# electro.net
KiCad netlist of a schematic drawn in EAGLE
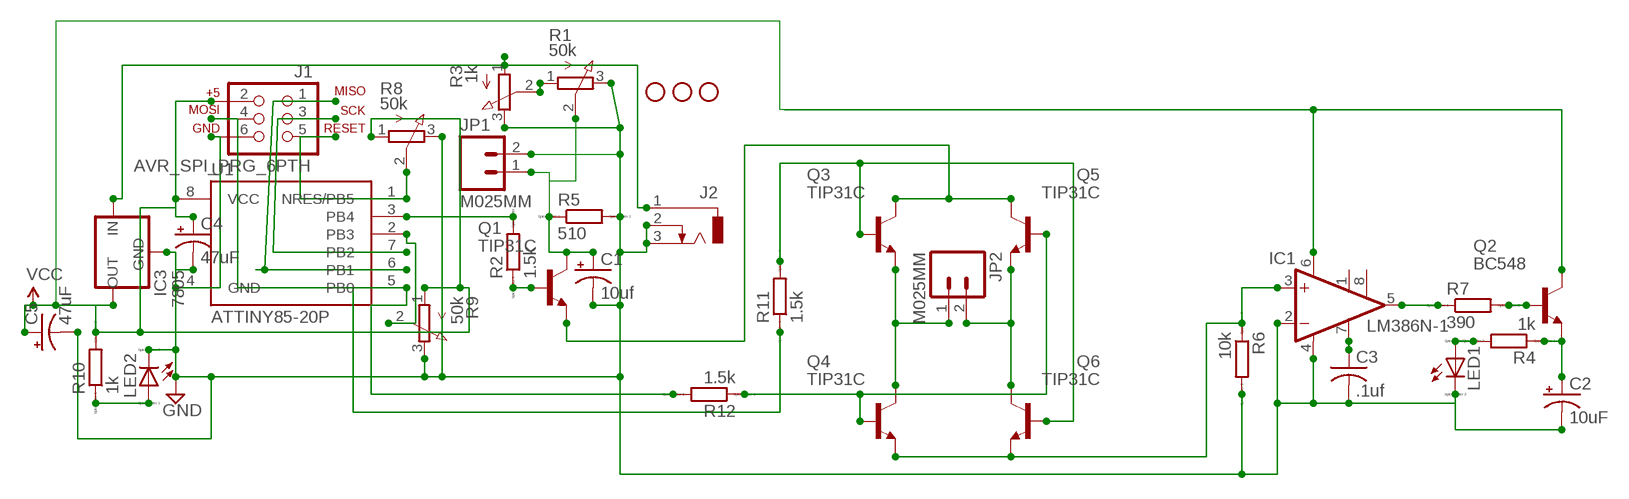
[diagram p0: schematic, sheet 1]

(export (version "E")
  (design (tool "Eeschema 10.0.6"))
  (components
    (comp (ref "C1")
      (value "10uf")
      (footprint "eagle-import:E2,5-6E")
      (libsource (lib "eagle-import") (part "CPOL-USE2,5-6E"))
    )
    (comp (ref "C2")
      (value "10uF")
      (footprint "eagle-import:E2,5-6E")
      (libsource (lib "eagle-import") (part "CPOL-USE2,5-6E"))
    )
    (comp (ref "C3")
      (value ".1uf")
      (footprint "eagle-import:C025-025X050")
      (libsource (lib "eagle-import") (part "C-US025-025X050"))
    )
    (comp (ref "C4")
      (value "47uF")
      (footprint "eagle-import:E2,5-6")
      (libsource (lib "eagle-import") (part "CPOL-USE2.5-6"))
    )
    (comp (ref "C5")
      (value "47uF")
      (footprint "eagle-import:E2,5-6")
      (libsource (lib "eagle-import") (part "CPOL-USE2.5-6"))
    )
    (comp (ref "IC1")
      (value "LM386N-1")
      (footprint "eagle-import:DIL08")
      (libsource (lib "eagle-import") (part "LM386?-N1"))
    )
    (comp (ref "IC3")
      (value "7805")
      (footprint "eagle-import:78XXL")
      (libsource (lib "eagle-import") (part "78XXL"))
    )
    (comp (ref "J1")
      (value "AVR_SPI_PRG_6PTH")
      (footprint "eagle-import:2X3")
      (libsource (lib "eagle-import") (part "AVR_SPI_PRG_6PTH"))
    )
    (comp (ref "J2")
      (value "DCJ0303")
      (footprint "eagle-import:DCJ0303")
      (libsource (lib "eagle-import") (part "DCJ0303"))
    )
    (comp (ref "JP1")
      (value "M025MM")
      (footprint "eagle-import:SCREWTERMINAL-5MM-2")
      (libsource (lib "eagle-import") (part "M025MM"))
    )
    (comp (ref "JP2")
      (value "M025MM")
      (footprint "eagle-import:SCREWTERMINAL-5MM-2")
      (libsource (lib "eagle-import") (part "M025MM"))
    )
    (comp (ref "LED1")
      (value "LED_ELD260")
      (footprint "eagle-import:LED_LD260")
      (libsource (lib "eagle-import") (part "LED_ELD260"))
    )
    (comp (ref "LED2")
      (value "LED_ELD260")
      (footprint "eagle-import:LED_LD260")
      (libsource (lib "eagle-import") (part "LED_ELD260"))
    )
    (comp (ref "Q1")
      (value "TIP31C")
      (footprint "eagle-import:TO220")
      (libsource (lib "eagle-import") (part "TIP31C"))
    )
    (comp (ref "Q2")
      (value "BC548")
      (footprint "eagle-import:TO92-EBC")
      (libsource (lib "eagle-import") (part "BC548"))
    )
    (comp (ref "Q3")
      (value "TIP31C")
      (footprint "eagle-import:TO220")
      (libsource (lib "eagle-import") (part "TIP31C"))
    )
    (comp (ref "Q4")
      (value "TIP31C")
      (footprint "eagle-import:TO220")
      (libsource (lib "eagle-import") (part "TIP31C"))
    )
    (comp (ref "Q5")
      (value "TIP31C")
      (footprint "eagle-import:TO220")
      (libsource (lib "eagle-import") (part "TIP31C"))
    )
    (comp (ref "Q6")
      (value "TIP31C")
      (footprint "eagle-import:TO220")
      (libsource (lib "eagle-import") (part "TIP31C"))
    )
    (comp (ref "R1")
      (value "50k")
      (footprint "eagle-import:3RP_1610N")
      (libsource (lib "eagle-import") (part "3RP/1610N"))
    )
    (comp (ref "R2")
      (value "1.5k")
      (footprint "eagle-import:0207_10")
      (libsource (lib "eagle-import") (part "R0207/10"))
    )
    (comp (ref "R3")
      (value "1k")
      (footprint "eagle-import:3RP_1610N")
      (libsource (lib "eagle-import") (part "3RP/1610N"))
    )
    (comp (ref "R4")
      (value "1k")
      (footprint "eagle-import:0207_10")
      (libsource (lib "eagle-import") (part "R0207/10"))
    )
    (comp (ref "R5")
      (value "510")
      (footprint "eagle-import:0207_10")
      (libsource (lib "eagle-import") (part "R0207/10"))
    )
    (comp (ref "R6")
      (value "10k")
      (footprint "eagle-import:0207_10")
      (libsource (lib "eagle-import") (part "R0207/10"))
    )
    (comp (ref "R7")
      (value "390")
      (footprint "eagle-import:0207_10")
      (libsource (lib "eagle-import") (part "R0207/10"))
    )
    (comp (ref "R8")
      (value "50k")
      (footprint "eagle-import:3RP_1610N")
      (libsource (lib "eagle-import") (part "3RP/1610N"))
    )
    (comp (ref "R9")
      (value "50k")
      (footprint "eagle-import:3RP_1610N")
      (libsource (lib "eagle-import") (part "3RP/1610N"))
    )
    (comp (ref "R10")
      (value "1k")
      (footprint "eagle-import:0207_10")
      (libsource (lib "eagle-import") (part "R0207/10"))
    )
    (comp (ref "R11")
      (value "1.5k")
      (footprint "eagle-import:0207_10")
      (libsource (lib "eagle-import") (part "R0207/10"))
    )
    (comp (ref "R12")
      (value "1.5k")
      (footprint "eagle-import:0207_10")
      (libsource (lib "eagle-import") (part "R0207/10"))
    )
    (comp (ref "STANDOFF2")
      (value "STAND-OFF")
      (footprint "eagle-import:STAND-OFF")
      (libsource (lib "eagle-import") (part "STAND-OFF"))
    )
    (comp (ref "STANDOFF3")
      (value "STAND-OFF")
      (footprint "eagle-import:STAND-OFF")
      (libsource (lib "eagle-import") (part "STAND-OFF"))
    )
    (comp (ref "STANDOFF4")
      (value "STAND-OFF")
      (footprint "eagle-import:STAND-OFF")
      (libsource (lib "eagle-import") (part "STAND-OFF"))
    )
    (comp (ref "U1")
      (value "ATTINY85-20P")
      (footprint "eagle-import:PDIP08_300MIL")
      (libsource (lib "eagle-import") (part "ATTINY85P-20"))
    )
  )
  (nets
    (net (code "1") (name "GND") (class "Default")
      (node (ref "C1") (pin "-") (pinfunction "-_-") (pintype "passive"))
      (node (ref "C2") (pin "-") (pinfunction "-_-") (pintype "passive"))
      (node (ref "C3") (pin "2") (pinfunction "2_2") (pintype "passive"))
      (node (ref "C4") (pin "-") (pinfunction "-_-") (pintype "passive"))
      (node (ref "C5") (pin "-") (pinfunction "-_-") (pintype "passive"))
      (node (ref "IC1") (pin "2") (pinfunction "-IN_2") (pintype "input"))
      (node (ref "IC1") (pin "4") (pinfunction "GND_4") (pintype "power_in"))
      (node (ref "IC3") (pin "GND") (pinfunction "GND_GND") (pintype "input"))
      (node (ref "J1") (pin "6") (pinfunction "6_6") (pintype "passive"))
      (node (ref "J2") (pin "2") (pinfunction "2_2") (pintype "passive"))
      (node (ref "J2") (pin "3") (pinfunction "3_3") (pintype "passive"))
      (node (ref "JP1") (pin "2") (pinfunction "2_2") (pintype "passive"))
      (node (ref "LED1") (pin "K") (pinfunction "C_K") (pintype "passive"))
      (node (ref "LED2") (pin "K") (pinfunction "C_K") (pintype "passive"))
      (node (ref "R1") (pin "3") (pinfunction "E_3") (pintype "passive"))
      (node (ref "R3") (pin "3") (pinfunction "E_3") (pintype "passive"))
      (node (ref "R5") (pin "2") (pinfunction "2_2") (pintype "passive"))
      (node (ref "R6") (pin "2") (pinfunction "2_2") (pintype "passive"))
      (node (ref "R8") (pin "3") (pinfunction "E_3") (pintype "passive"))
      (node (ref "R9") (pin "3") (pinfunction "E_3") (pintype "passive"))
      (node (ref "U1") (pin "4") (pinfunction "GND_4") (pintype "power_in"))
    )
    (net (code "2") (name "Net-(C2-Pad+)") (class "Default")
      (node (ref "C2") (pin "+") (pinfunction "+_+") (pintype "passive"))
      (node (ref "Q2") (pin "E") (pinfunction "E_E") (pintype "passive"))
      (node (ref "R4") (pin "1") (pinfunction "1_1") (pintype "passive"))
    )
    (net (code "3") (name "Net-(IC1-+IN)") (class "Default")
      (node (ref "IC1") (pin "3") (pinfunction "+IN_3") (pintype "input"))
      (node (ref "Q4") (pin "3") (pinfunction "E_3") (pintype "passive"))
      (node (ref "Q6") (pin "3") (pinfunction "E_3") (pintype "passive"))
      (node (ref "R6") (pin "1") (pinfunction "1_1") (pintype "passive"))
    )
    (net (code "4") (name "Net-(IC1-BYPASS)") (class "Default")
      (node (ref "C3") (pin "1") (pinfunction "1_1") (pintype "passive"))
      (node (ref "IC1") (pin "7") (pinfunction "BYPASS_7") (pintype "passive"))
    )
    (net (code "5") (name "Net-(IC1-OUT)") (class "Default")
      (node (ref "IC1") (pin "5") (pinfunction "OUT_5") (pintype "output"))
      (node (ref "R7") (pin "1") (pinfunction "1_1") (pintype "passive"))
    )
    (net (code "6") (name "Net-(LED1-PadA)") (class "Default")
      (node (ref "LED1") (pin "A") (pinfunction "A_A") (pintype "passive"))
      (node (ref "R4") (pin "2") (pinfunction "2_2") (pintype "passive"))
    )
    (net (code "7") (name "Net-(LED2-PadA)") (class "Default")
      (node (ref "LED2") (pin "A") (pinfunction "A_A") (pintype "passive"))
      (node (ref "R10") (pin "1") (pinfunction "1_1") (pintype "passive"))
    )
    (net (code "8") (name "Net-(Q1-B)") (class "Default")
      (node (ref "Q1") (pin "1") (pinfunction "B_1") (pintype "passive"))
      (node (ref "R2") (pin "1") (pinfunction "1_1") (pintype "passive"))
    )
    (net (code "9") (name "Net-(Q1-C)") (class "Default")
      (node (ref "C1") (pin "+") (pinfunction "+_+") (pintype "passive"))
      (node (ref "JP1") (pin "1") (pinfunction "1_1") (pintype "passive"))
      (node (ref "Q1") (pin "2") (pinfunction "C_2") (pintype "passive"))
      (node (ref "R1") (pin "2") (pinfunction "S_2") (pintype "passive"))
      (node (ref "R5") (pin "1") (pinfunction "1_1") (pintype "passive"))
    )
    (net (code "10") (name "Net-(Q1-E)") (class "Default")
      (node (ref "Q1") (pin "3") (pinfunction "E_3") (pintype "passive"))
      (node (ref "Q3") (pin "2") (pinfunction "C_2") (pintype "passive"))
      (node (ref "Q5") (pin "2") (pinfunction "C_2") (pintype "passive"))
    )
    (net (code "11") (name "Net-(Q2-PadB)") (class "Default")
      (node (ref "Q2") (pin "B") (pinfunction "B_B") (pintype "passive"))
      (node (ref "R7") (pin "2") (pinfunction "2_2") (pintype "passive"))
    )
    (net (code "12") (name "Net-(Q3-B)") (class "Default")
      (node (ref "Q3") (pin "1") (pinfunction "B_1") (pintype "passive"))
      (node (ref "Q6") (pin "1") (pinfunction "B_1") (pintype "passive"))
      (node (ref "R11") (pin "2") (pinfunction "2_2") (pintype "passive"))
    )
    (net (code "13") (name "Net-(Q3-E)") (class "Default")
      (node (ref "JP2") (pin "1") (pinfunction "1_1") (pintype "passive"))
      (node (ref "Q3") (pin "3") (pinfunction "E_3") (pintype "passive"))
      (node (ref "Q4") (pin "2") (pinfunction "C_2") (pintype "passive"))
    )
    (net (code "14") (name "Net-(Q4-B)") (class "Default")
      (node (ref "Q4") (pin "1") (pinfunction "B_1") (pintype "passive"))
      (node (ref "Q5") (pin "1") (pinfunction "B_1") (pintype "passive"))
      (node (ref "R12") (pin "1") (pinfunction "1_1") (pintype "passive"))
    )
    (net (code "15") (name "Net-(Q5-E)") (class "Default")
      (node (ref "JP2") (pin "2") (pinfunction "2_2") (pintype "passive"))
      (node (ref "Q5") (pin "3") (pinfunction "E_3") (pintype "passive"))
      (node (ref "Q6") (pin "2") (pinfunction "C_2") (pintype "passive"))
    )
    (net (code "16") (name "Net-(R1-A)") (class "Default")
      (node (ref "R1") (pin "1") (pinfunction "A_1") (pintype "passive"))
      (node (ref "R3") (pin "2") (pinfunction "S_2") (pintype "passive"))
    )
    (net (code "17") (name "Net-(R3-A)") (class "Default")
      (node (ref "IC3") (pin "IN") (pinfunction "IN_IN") (pintype "input"))
      (node (ref "J2") (pin "1") (pinfunction "1_1") (pintype "passive"))
      (node (ref "R3") (pin "1") (pinfunction "A_1") (pintype "passive"))
    )
    (net (code "18") (name "Net-(R8-S)") (class "Default")
      (node (ref "J1") (pin "5") (pinfunction "5_5") (pintype "passive"))
      (node (ref "R8") (pin "2") (pinfunction "S_2") (pintype "passive"))
      (node (ref "U1") (pin "1") (pinfunction "NRES/PB5_1") (pintype "bidirectional"))
    )
    (net (code "19") (name "Net-(R9-S)") (class "Default")
      (node (ref "R9") (pin "2") (pinfunction "S_2") (pintype "passive"))
      (node (ref "U1") (pin "2") (pinfunction "PB3_2") (pintype "bidirectional"))
    )
    (net (code "20") (name "Net-(U1-PB0)") (class "Default")
      (node (ref "J1") (pin "4") (pinfunction "4_4") (pintype "passive"))
      (node (ref "R11") (pin "1") (pinfunction "1_1") (pintype "passive"))
      (node (ref "R12") (pin "2") (pinfunction "2_2") (pintype "passive"))
      (node (ref "U1") (pin "5") (pinfunction "PB0_5") (pintype "bidirectional"))
    )
    (net (code "21") (name "Net-(U1-PB1)") (class "Default")
      (node (ref "J1") (pin "1") (pinfunction "1_1") (pintype "passive"))
      (node (ref "U1") (pin "6") (pinfunction "PB1_6") (pintype "bidirectional"))
    )
    (net (code "22") (name "Net-(U1-PB2)") (class "Default")
      (node (ref "J1") (pin "3") (pinfunction "3_3") (pintype "passive"))
      (node (ref "U1") (pin "7") (pinfunction "PB2_7") (pintype "bidirectional"))
    )
    (net (code "23") (name "Net-(U1-PB4)") (class "Default")
      (node (ref "R2") (pin "2") (pinfunction "2_2") (pintype "passive"))
      (node (ref "U1") (pin "3") (pinfunction "PB4_3") (pintype "bidirectional"))
    )
    (net (code "24") (name "VCC") (class "Default")
      (node (ref "C4") (pin "+") (pinfunction "+_+") (pintype "passive"))
      (node (ref "C5") (pin "+") (pinfunction "+_+") (pintype "passive"))
      (node (ref "IC1") (pin "6") (pinfunction "VS_6") (pintype "power_in"))
      (node (ref "IC3") (pin "OUT") (pinfunction "OUT_OUT") (pintype "passive"))
      (node (ref "J1") (pin "2") (pinfunction "2_2") (pintype "passive"))
      (node (ref "Q2") (pin "C") (pinfunction "C_C") (pintype "passive"))
      (node (ref "R10") (pin "2") (pinfunction "2_2") (pintype "passive"))
      (node (ref "R8") (pin "1") (pinfunction "A_1") (pintype "passive"))
      (node (ref "R9") (pin "1") (pinfunction "A_1") (pintype "passive"))
      (node (ref "U1") (pin "8") (pinfunction "VCC_8") (pintype "power_in"))
    )
    (net (code "25") (name "unconnected-(IC1-GAIN-Pad1)") (class "Default")
      (node (ref "IC1") (pin "1") (pinfunction "GAIN_1") (pintype "passive"))
    )
    (net (code "26") (name "unconnected-(IC1-GAIN-Pad8)") (class "Default")
      (node (ref "IC1") (pin "8") (pinfunction "GAIN_8") (pintype "passive"))
    )
  )
)
